# Lights-ctrl_rev00.net
KiCad netlist of a schematic drawn in EAGLE
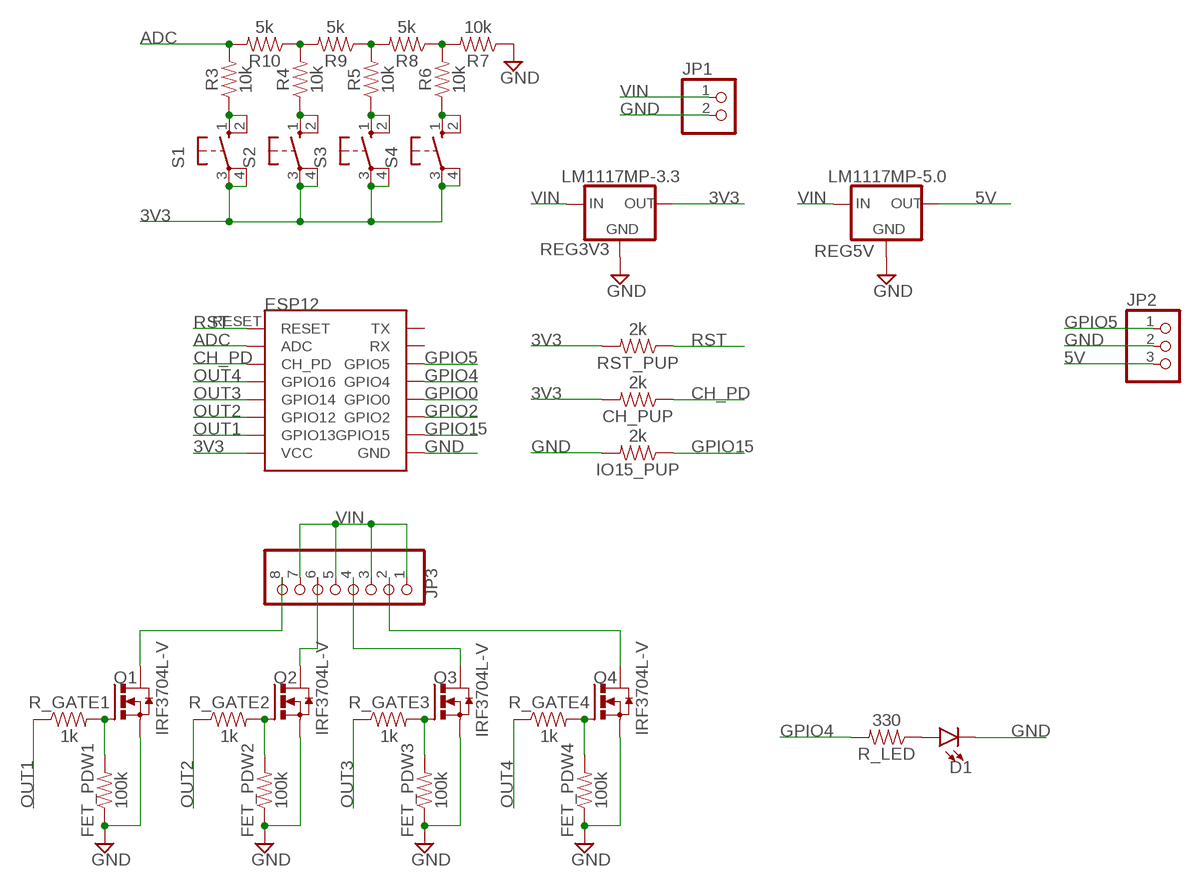
[diagram p0: schematic, sheet 1]

(export (version "E")
  (design (tool "Eeschema 10.0.6"))
  (components
    (comp (ref "CH_PUP")
      (value "2k")
      (footprint "eagle-import:0603")
      (libsource (lib "eagle-import") (part "200KOHM-0603-1/10W-1%"))
    )
    (comp (ref "D1")
      (value "LED5MM-KIT")
      (footprint "eagle-import:LED_5MM-KIT")
      (libsource (lib "eagle-import") (part "LED5MM-KIT"))
    )
    (comp (ref "FET_PDW1")
      (value "100k")
      (footprint "eagle-import:0603")
      (libsource (lib "eagle-import") (part "200KOHM-0603-1/10W-1%"))
    )
    (comp (ref "FET_PDW2")
      (value "100k")
      (footprint "eagle-import:0603")
      (libsource (lib "eagle-import") (part "200KOHM-0603-1/10W-1%"))
    )
    (comp (ref "FET_PDW3")
      (value "100k")
      (footprint "eagle-import:0603")
      (libsource (lib "eagle-import") (part "200KOHM-0603-1/10W-1%"))
    )
    (comp (ref "FET_PDW4")
      (value "100k")
      (footprint "eagle-import:0603")
      (libsource (lib "eagle-import") (part "200KOHM-0603-1/10W-1%"))
    )
    (comp (ref "IO15_PUP")
      (value "2k")
      (footprint "eagle-import:0603")
      (libsource (lib "eagle-import") (part "200KOHM-0603-1/10W-1%"))
    )
    (comp (ref "JP1")
      (value "PINHD-1X2")
      (footprint "eagle-import:1X02")
      (libsource (lib "eagle-import") (part "PINHD-1X2"))
    )
    (comp (ref "JP2")
      (value "PINHD-1X3")
      (footprint "eagle-import:1X03")
      (libsource (lib "eagle-import") (part "PINHD-1X3"))
    )
    (comp (ref "JP3")
      (value "PINHD-1X8/90")
      (footprint "eagle-import:1X08_90")
      (libsource (lib "eagle-import") (part "PINHD-1X8/90"))
    )
    (comp (ref "Q1")
      (value "IRF3704L-V")
      (footprint "eagle-import:TO262-V")
      (libsource (lib "eagle-import") (part "IRF3704L-V"))
    )
    (comp (ref "Q2")
      (value "IRF3704L-V")
      (footprint "eagle-import:TO262-V")
      (libsource (lib "eagle-import") (part "IRF3704L-V"))
    )
    (comp (ref "Q3")
      (value "IRF3704L-V")
      (footprint "eagle-import:TO262-V")
      (libsource (lib "eagle-import") (part "IRF3704L-V"))
    )
    (comp (ref "Q4")
      (value "IRF3704L-V")
      (footprint "eagle-import:TO262-V")
      (libsource (lib "eagle-import") (part "IRF3704L-V"))
    )
    (comp (ref "R3")
      (value "10k")
      (footprint "eagle-import:0603")
      (libsource (lib "eagle-import") (part "200KOHM-0603-1/10W-1%"))
    )
    (comp (ref "R4")
      (value "10k")
      (footprint "eagle-import:0603")
      (libsource (lib "eagle-import") (part "200KOHM-0603-1/10W-1%"))
    )
    (comp (ref "R5")
      (value "10k")
      (footprint "eagle-import:0603")
      (libsource (lib "eagle-import") (part "200KOHM-0603-1/10W-1%"))
    )
    (comp (ref "R6")
      (value "10k")
      (footprint "eagle-import:0603")
      (libsource (lib "eagle-import") (part "200KOHM-0603-1/10W-1%"))
    )
    (comp (ref "R7")
      (value "10k")
      (footprint "eagle-import:0603")
      (libsource (lib "eagle-import") (part "200KOHM-0603-1/10W-1%"))
    )
    (comp (ref "R8")
      (value "5k")
      (footprint "eagle-import:0603")
      (libsource (lib "eagle-import") (part "200KOHM-0603-1/10W-1%"))
    )
    (comp (ref "R9")
      (value "5k")
      (footprint "eagle-import:0603")
      (libsource (lib "eagle-import") (part "200KOHM-0603-1/10W-1%"))
    )
    (comp (ref "R10")
      (value "5k")
      (footprint "eagle-import:0603")
      (libsource (lib "eagle-import") (part "200KOHM-0603-1/10W-1%"))
    )
    (comp (ref "REG3V3")
      (value "LM1117MP-3.3")
      (footprint "eagle-import:SOT223")
      (fields (field (name "MF") "Texas Instruments"))
      (libsource (lib "eagle-import") (part "LM1117?-MP3.3"))
    )
    (comp (ref "REG5V")
      (value "LM1117MP-5.0")
      (footprint "eagle-import:SOT223")
      (fields (field (name "MF") "Texas Instruments"))
      (libsource (lib "eagle-import") (part "LM1117?-MP5.0"))
    )
    (comp (ref "RST_PUP")
      (value "2k")
      (footprint "eagle-import:0603")
      (libsource (lib "eagle-import") (part "200KOHM-0603-1/10W-1%"))
    )
    (comp (ref "R_GATE1")
      (value "1k")
      (footprint "eagle-import:0603")
      (libsource (lib "eagle-import") (part "200KOHM-0603-1/10W-1%"))
    )
    (comp (ref "R_GATE2")
      (value "1k")
      (footprint "eagle-import:0603")
      (libsource (lib "eagle-import") (part "200KOHM-0603-1/10W-1%"))
    )
    (comp (ref "R_GATE3")
      (value "1k")
      (footprint "eagle-import:0603")
      (libsource (lib "eagle-import") (part "200KOHM-0603-1/10W-1%"))
    )
    (comp (ref "R_GATE4")
      (value "1k")
      (footprint "eagle-import:0603")
      (libsource (lib "eagle-import") (part "200KOHM-0603-1/10W-1%"))
    )
    (comp (ref "R_LED")
      (value "330")
      (footprint "eagle-import:0603")
      (libsource (lib "eagle-import") (part "200KOHM-0603-1/10W-1%"))
    )
    (comp (ref "S1")
      (value "10-XX")
      (footprint "eagle-import:B3F-10XX")
      (fields (field (name "MPN") "B3F-1000"))
      (libsource (lib "eagle-import") (part "10-XX"))
    )
    (comp (ref "S2")
      (value "10-XX")
      (footprint "eagle-import:B3F-10XX")
      (fields (field (name "MPN") "B3F-1000"))
      (libsource (lib "eagle-import") (part "10-XX"))
    )
    (comp (ref "S3")
      (value "10-XX")
      (footprint "eagle-import:B3F-10XX")
      (fields (field (name "MPN") "B3F-1000"))
      (libsource (lib "eagle-import") (part "10-XX"))
    )
    (comp (ref "S4")
      (value "10-XX")
      (footprint "eagle-import:B3F-10XX")
      (fields (field (name "MPN") "B3F-1000"))
      (libsource (lib "eagle-import") (part "10-XX"))
    )
    (comp (ref "U$1")
      (value "ESP12E-CASTELLATED")
      (footprint "eagle-import:ESP12E-CASTELLATED")
      (libsource (lib "eagle-import") (part "ESP12E-CASTELLATED"))
    )
  )
  (nets
    (net (code "1") (name "/3V3") (class "Default")
      (node (ref "CH_PUP") (pin "2") (pinfunction "2_2") (pintype "passive"))
      (node (ref "REG3V3") (pin "2") (pinfunction "OUT_2") (pintype "passive"))
      (node (ref "REG3V3") (pin "4") (pinfunction "OUT_4") (pintype "passive"))
      (node (ref "RST_PUP") (pin "2") (pinfunction "2_2") (pintype "passive"))
      (node (ref "S1") (pin "3") (pinfunction "P_3") (pintype "passive"))
      (node (ref "S1") (pin "4") (pinfunction "P1_4") (pintype "passive"))
      (node (ref "S2") (pin "3") (pinfunction "P_3") (pintype "passive"))
      (node (ref "S2") (pin "4") (pinfunction "P1_4") (pintype "passive"))
      (node (ref "S3") (pin "3") (pinfunction "P_3") (pintype "passive"))
      (node (ref "S3") (pin "4") (pinfunction "P1_4") (pintype "passive"))
      (node (ref "S4") (pin "3") (pinfunction "P_3") (pintype "passive"))
      (node (ref "S4") (pin "4") (pinfunction "P1_4") (pintype "passive"))
      (node (ref "U$1") (pin "VCC") (pinfunction "VCC_VCC") (pintype "bidirectional"))
    )
    (net (code "2") (name "/5V") (class "Default")
      (node (ref "JP2") (pin "3") (pinfunction "3_3") (pintype "passive"))
      (node (ref "REG5V") (pin "2") (pinfunction "OUT_2") (pintype "passive"))
      (node (ref "REG5V") (pin "4") (pinfunction "OUT_4") (pintype "passive"))
    )
    (net (code "3") (name "/ADC") (class "Default")
      (node (ref "R10") (pin "2") (pinfunction "2_2") (pintype "passive"))
      (node (ref "R3") (pin "2") (pinfunction "2_2") (pintype "passive"))
      (node (ref "U$1") (pin "ADC") (pinfunction "ADC_ADC") (pintype "bidirectional"))
    )
    (net (code "4") (name "/CH_PD") (class "Default")
      (node (ref "CH_PUP") (pin "1") (pinfunction "1_1") (pintype "passive"))
      (node (ref "U$1") (pin "CH_PD") (pinfunction "CH_PD_CH_PD") (pintype "bidirectional"))
    )
    (net (code "5") (name "/GPIO0") (class "Default")
      (node (ref "U$1") (pin "GPIO0") (pinfunction "GPIO0_GPIO0") (pintype "bidirectional"))
    )
    (net (code "6") (name "/GPIO2") (class "Default")
      (node (ref "U$1") (pin "GPIO2") (pinfunction "GPIO2_GPIO2") (pintype "bidirectional"))
    )
    (net (code "7") (name "/GPIO4") (class "Default")
      (node (ref "R_LED") (pin "2") (pinfunction "2_2") (pintype "passive"))
      (node (ref "U$1") (pin "GPIO4") (pinfunction "GPIO4_GPIO4") (pintype "bidirectional"))
    )
    (net (code "8") (name "/GPIO5") (class "Default")
      (node (ref "JP2") (pin "1") (pinfunction "1_1") (pintype "passive"))
      (node (ref "U$1") (pin "GPIO5") (pinfunction "GPIO5_GPIO5") (pintype "bidirectional"))
    )
    (net (code "9") (name "/GPIO15") (class "Default")
      (node (ref "IO15_PUP") (pin "1") (pinfunction "1_1") (pintype "passive"))
      (node (ref "U$1") (pin "GPIO15") (pinfunction "GPIO15_GPIO15") (pintype "bidirectional"))
    )
    (net (code "10") (name "/OUT1") (class "Default")
      (node (ref "R_GATE1") (pin "1") (pinfunction "1_1") (pintype "passive"))
      (node (ref "U$1") (pin "GPIO13") (pinfunction "GPIO13_GPIO13") (pintype "bidirectional"))
    )
    (net (code "11") (name "/OUT2") (class "Default")
      (node (ref "R_GATE2") (pin "1") (pinfunction "1_1") (pintype "passive"))
      (node (ref "U$1") (pin "GPIO12") (pinfunction "GPIO12_GPIO12") (pintype "bidirectional"))
    )
    (net (code "12") (name "/OUT3") (class "Default")
      (node (ref "R_GATE3") (pin "1") (pinfunction "1_1") (pintype "passive"))
      (node (ref "U$1") (pin "GPIO14") (pinfunction "GPIO14_GPIO14") (pintype "bidirectional"))
    )
    (net (code "13") (name "/OUT4") (class "Default")
      (node (ref "R_GATE4") (pin "1") (pinfunction "1_1") (pintype "passive"))
      (node (ref "U$1") (pin "GPIO16") (pinfunction "GPIO16_GPIO16") (pintype "bidirectional"))
    )
    (net (code "14") (name "/RST") (class "Default")
      (node (ref "RST_PUP") (pin "1") (pinfunction "1_1") (pintype "passive"))
      (node (ref "U$1") (pin "RESET") (pinfunction "RESET_RESET") (pintype "bidirectional"))
    )
    (net (code "15") (name "/VIN") (class "Default")
      (node (ref "JP1") (pin "1") (pinfunction "1_1") (pintype "passive"))
      (node (ref "JP3") (pin "1") (pinfunction "1_1") (pintype "passive"))
      (node (ref "JP3") (pin "3") (pinfunction "3_3") (pintype "passive"))
      (node (ref "JP3") (pin "5") (pinfunction "5_5") (pintype "passive"))
      (node (ref "JP3") (pin "7") (pinfunction "7_7") (pintype "passive"))
      (node (ref "REG3V3") (pin "3") (pinfunction "IN_3") (pintype "input"))
      (node (ref "REG5V") (pin "3") (pinfunction "IN_3") (pintype "input"))
    )
    (net (code "16") (name "GND") (class "Default")
      (node (ref "D1") (pin "K") (pinfunction "C_K") (pintype "passive"))
      (node (ref "FET_PDW1") (pin "1") (pinfunction "1_1") (pintype "passive"))
      (node (ref "FET_PDW2") (pin "1") (pinfunction "1_1") (pintype "passive"))
      (node (ref "FET_PDW3") (pin "1") (pinfunction "1_1") (pintype "passive"))
      (node (ref "FET_PDW4") (pin "1") (pinfunction "1_1") (pintype "passive"))
      (node (ref "IO15_PUP") (pin "2") (pinfunction "2_2") (pintype "passive"))
      (node (ref "JP1") (pin "2") (pinfunction "2_2") (pintype "passive"))
      (node (ref "JP2") (pin "2") (pinfunction "2_2") (pintype "passive"))
      (node (ref "Q1") (pin "3") (pinfunction "S_3") (pintype "passive"))
      (node (ref "Q2") (pin "3") (pinfunction "S_3") (pintype "passive"))
      (node (ref "Q3") (pin "3") (pinfunction "S_3") (pintype "passive"))
      (node (ref "Q4") (pin "3") (pinfunction "S_3") (pintype "passive"))
      (node (ref "R7") (pin "1") (pinfunction "1_1") (pintype "passive"))
      (node (ref "REG3V3") (pin "1") (pinfunction "GND_1") (pintype "input"))
      (node (ref "REG5V") (pin "1") (pinfunction "GND_1") (pintype "input"))
      (node (ref "U$1") (pin "GND") (pinfunction "GND_GND") (pintype "bidirectional"))
    )
    (net (code "17") (name "Net-(D1-PadA)") (class "Default")
      (node (ref "D1") (pin "A") (pinfunction "A_A") (pintype "passive"))
      (node (ref "R_LED") (pin "1") (pinfunction "1_1") (pintype "passive"))
    )
    (net (code "18") (name "Net-(Q1-D)") (class "Default")
      (node (ref "JP3") (pin "8") (pinfunction "8_8") (pintype "passive"))
      (node (ref "Q1") (pin "2") (pinfunction "D_2") (pintype "passive"))
    )
    (net (code "19") (name "Net-(Q1-G)") (class "Default")
      (node (ref "FET_PDW1") (pin "2") (pinfunction "2_2") (pintype "passive"))
      (node (ref "Q1") (pin "1") (pinfunction "G_1") (pintype "passive"))
      (node (ref "R_GATE1") (pin "2") (pinfunction "2_2") (pintype "passive"))
    )
    (net (code "20") (name "Net-(Q2-D)") (class "Default")
      (node (ref "JP3") (pin "6") (pinfunction "6_6") (pintype "passive"))
      (node (ref "Q2") (pin "2") (pinfunction "D_2") (pintype "passive"))
    )
    (net (code "21") (name "Net-(Q2-G)") (class "Default")
      (node (ref "FET_PDW2") (pin "2") (pinfunction "2_2") (pintype "passive"))
      (node (ref "Q2") (pin "1") (pinfunction "G_1") (pintype "passive"))
      (node (ref "R_GATE2") (pin "2") (pinfunction "2_2") (pintype "passive"))
    )
    (net (code "22") (name "Net-(Q3-D)") (class "Default")
      (node (ref "JP3") (pin "4") (pinfunction "4_4") (pintype "passive"))
      (node (ref "Q3") (pin "2") (pinfunction "D_2") (pintype "passive"))
    )
    (net (code "23") (name "Net-(Q3-G)") (class "Default")
      (node (ref "FET_PDW3") (pin "2") (pinfunction "2_2") (pintype "passive"))
      (node (ref "Q3") (pin "1") (pinfunction "G_1") (pintype "passive"))
      (node (ref "R_GATE3") (pin "2") (pinfunction "2_2") (pintype "passive"))
    )
    (net (code "24") (name "Net-(Q4-D)") (class "Default")
      (node (ref "JP3") (pin "2") (pinfunction "2_2") (pintype "passive"))
      (node (ref "Q4") (pin "2") (pinfunction "D_2") (pintype "passive"))
    )
    (net (code "25") (name "Net-(Q4-G)") (class "Default")
      (node (ref "FET_PDW4") (pin "2") (pinfunction "2_2") (pintype "passive"))
      (node (ref "Q4") (pin "1") (pinfunction "G_1") (pintype "passive"))
      (node (ref "R_GATE4") (pin "2") (pinfunction "2_2") (pintype "passive"))
    )
    (net (code "26") (name "Net-(R5-Pad2)") (class "Default")
      (node (ref "R5") (pin "2") (pinfunction "2_2") (pintype "passive"))
      (node (ref "R8") (pin "2") (pinfunction "2_2") (pintype "passive"))
      (node (ref "R9") (pin "1") (pinfunction "1_1") (pintype "passive"))
    )
    (net (code "27") (name "Net-(R6-Pad2)") (class "Default")
      (node (ref "R6") (pin "2") (pinfunction "2_2") (pintype "passive"))
      (node (ref "R7") (pin "2") (pinfunction "2_2") (pintype "passive"))
      (node (ref "R8") (pin "1") (pinfunction "1_1") (pintype "passive"))
    )
    (net (code "28") (name "Net-(R10-Pad1)") (class "Default")
      (node (ref "R10") (pin "1") (pinfunction "1_1") (pintype "passive"))
      (node (ref "R4") (pin "2") (pinfunction "2_2") (pintype "passive"))
      (node (ref "R9") (pin "2") (pinfunction "2_2") (pintype "passive"))
    )
    (net (code "29") (name "Net-(S1-S)") (class "Default")
      (node (ref "R3") (pin "1") (pinfunction "1_1") (pintype "passive"))
      (node (ref "S1") (pin "1") (pinfunction "S_1") (pintype "passive"))
      (node (ref "S1") (pin "2") (pinfunction "S1_2") (pintype "passive"))
    )
    (net (code "30") (name "Net-(S2-S)") (class "Default")
      (node (ref "R4") (pin "1") (pinfunction "1_1") (pintype "passive"))
      (node (ref "S2") (pin "1") (pinfunction "S_1") (pintype "passive"))
      (node (ref "S2") (pin "2") (pinfunction "S1_2") (pintype "passive"))
    )
    (net (code "31") (name "Net-(S3-S)") (class "Default")
      (node (ref "R5") (pin "1") (pinfunction "1_1") (pintype "passive"))
      (node (ref "S3") (pin "1") (pinfunction "S_1") (pintype "passive"))
      (node (ref "S3") (pin "2") (pinfunction "S1_2") (pintype "passive"))
    )
    (net (code "32") (name "Net-(S4-S)") (class "Default")
      (node (ref "R6") (pin "1") (pinfunction "1_1") (pintype "passive"))
      (node (ref "S4") (pin "1") (pinfunction "S_1") (pintype "passive"))
      (node (ref "S4") (pin "2") (pinfunction "S1_2") (pintype "passive"))
    )
    (net (code "33") (name "unconnected-(U$1-PadRX)") (class "Default")
      (node (ref "U$1") (pin "RX") (pinfunction "RX_RX") (pintype "bidirectional"))
    )
    (net (code "34") (name "unconnected-(U$1-PadTX)") (class "Default")
      (node (ref "U$1") (pin "TX") (pinfunction "TX_TX") (pintype "bidirectional"))
    )
  )
)
